# RASPBERRY_PI.net
KiCad netlist of a schematic drawn in Altium Designer
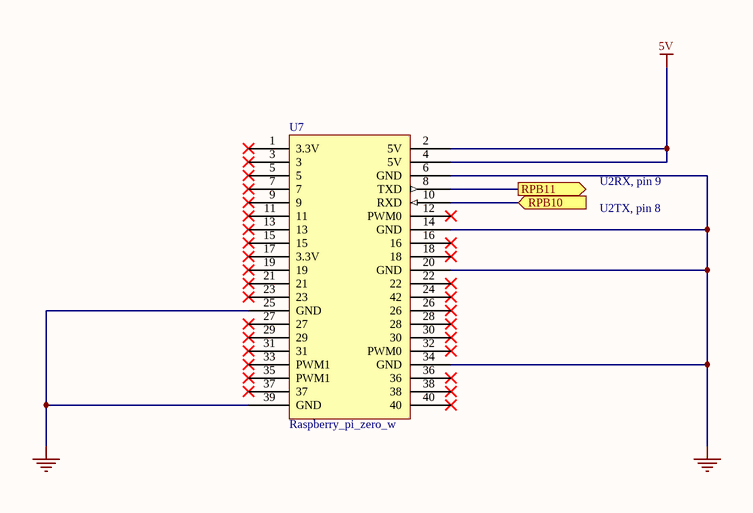
[diagram p0: RASPBERRY_PI.SchDoc]

(export (version "E")
  (design (tool "Eeschema 10.0.6"))
  (components
    (comp (ref "U7")
      (value "Raspberry_pi_zero_w")
      (footprint "RASPB")
      (libsource (lib "Schlib1") (part "Raspberry_pi_zero_w"))
    )
  )
  (nets
    (net (code "1") (name "/RPB10") (class "Default")
      (node (ref "U7") (pin "10") (pinfunction "RXD_10") (pintype "input"))
    )
    (net (code "2") (name "/RPB11") (class "Default")
      (node (ref "U7") (pin "8") (pinfunction "TXD_8") (pintype "output"))
    )
    (net (code "3") (name "5V") (class "Default")
      (node (ref "U7") (pin "2") (pinfunction "5V_2") (pintype "power_in"))
      (node (ref "U7") (pin "4") (pinfunction "5V_4") (pintype "power_in"))
    )
    (net (code "4") (name "GND") (class "Default")
      (node (ref "U7") (pin "14") (pinfunction "GND_14") (pintype "power_in"))
      (node (ref "U7") (pin "20") (pinfunction "GND_20") (pintype "power_in"))
      (node (ref "U7") (pin "25") (pinfunction "GND_25") (pintype "power_in"))
      (node (ref "U7") (pin "34") (pinfunction "GND_34") (pintype "power_in"))
      (node (ref "U7") (pin "39") (pinfunction "GND_39") (pintype "power_in"))
      (node (ref "U7") (pin "6") (pinfunction "GND_6") (pintype "power_in"))
    )
    (net (code "5") (name "unconnected-(U7-3.3V-Pad1)") (class "Default")
      (node (ref "U7") (pin "1") (pinfunction "3.3V_1") (pintype "power_in+no_connect"))
    )
    (net (code "6") (name "unconnected-(U7-3.3V-Pad17)") (class "Default")
      (node (ref "U7") (pin "17") (pinfunction "3.3V_17") (pintype "power_in+no_connect"))
    )
    (net (code "7") (name "unconnected-(U7-42-Pad24)") (class "Default")
      (node (ref "U7") (pin "24") (pinfunction "42_24") (pintype "passive+no_connect"))
    )
    (net (code "8") (name "unconnected-(U7-PWM0-Pad12)") (class "Default")
      (node (ref "U7") (pin "12") (pinfunction "PWM0_12") (pintype "passive+no_connect"))
    )
    (net (code "9") (name "unconnected-(U7-PWM0-Pad32)") (class "Default")
      (node (ref "U7") (pin "32") (pinfunction "PWM0_32") (pintype "passive+no_connect"))
    )
    (net (code "10") (name "unconnected-(U7-PWM1-Pad33)") (class "Default")
      (node (ref "U7") (pin "33") (pinfunction "PWM1_33") (pintype "passive+no_connect"))
    )
    (net (code "11") (name "unconnected-(U7-PWM1-Pad35)") (class "Default")
      (node (ref "U7") (pin "35") (pinfunction "PWM1_35") (pintype "passive+no_connect"))
    )
    (net (code "12") (name "unconnected-(U7-Pad3)") (class "Default")
      (node (ref "U7") (pin "3") (pinfunction "3_3") (pintype "passive+no_connect"))
    )
    (net (code "13") (name "unconnected-(U7-Pad5)") (class "Default")
      (node (ref "U7") (pin "5") (pinfunction "5_5") (pintype "passive+no_connect"))
    )
    (net (code "14") (name "unconnected-(U7-Pad7)") (class "Default")
      (node (ref "U7") (pin "7") (pinfunction "7_7") (pintype "passive+no_connect"))
    )
    (net (code "15") (name "unconnected-(U7-Pad9)") (class "Default")
      (node (ref "U7") (pin "9") (pinfunction "9_9") (pintype "passive+no_connect"))
    )
    (net (code "16") (name "unconnected-(U7-Pad11)") (class "Default")
      (node (ref "U7") (pin "11") (pinfunction "11_11") (pintype "passive+no_connect"))
    )
    (net (code "17") (name "unconnected-(U7-Pad13)") (class "Default")
      (node (ref "U7") (pin "13") (pinfunction "13_13") (pintype "passive+no_connect"))
    )
    (net (code "18") (name "unconnected-(U7-Pad15)") (class "Default")
      (node (ref "U7") (pin "15") (pinfunction "15_15") (pintype "passive+no_connect"))
    )
    (net (code "19") (name "unconnected-(U7-Pad16)") (class "Default")
      (node (ref "U7") (pin "16") (pinfunction "16_16") (pintype "passive+no_connect"))
    )
    (net (code "20") (name "unconnected-(U7-Pad18)") (class "Default")
      (node (ref "U7") (pin "18") (pinfunction "18_18") (pintype "passive+no_connect"))
    )
    (net (code "21") (name "unconnected-(U7-Pad19)") (class "Default")
      (node (ref "U7") (pin "19") (pinfunction "19_19") (pintype "passive+no_connect"))
    )
    (net (code "22") (name "unconnected-(U7-Pad21)") (class "Default")
      (node (ref "U7") (pin "21") (pinfunction "21_21") (pintype "passive+no_connect"))
    )
    (net (code "23") (name "unconnected-(U7-Pad22)") (class "Default")
      (node (ref "U7") (pin "22") (pinfunction "22_22") (pintype "passive+no_connect"))
    )
    (net (code "24") (name "unconnected-(U7-Pad23)") (class "Default")
      (node (ref "U7") (pin "23") (pinfunction "23_23") (pintype "passive+no_connect"))
    )
    (net (code "25") (name "unconnected-(U7-Pad26)") (class "Default")
      (node (ref "U7") (pin "26") (pinfunction "26_26") (pintype "passive+no_connect"))
    )
    (net (code "26") (name "unconnected-(U7-Pad27)") (class "Default")
      (node (ref "U7") (pin "27") (pinfunction "27_27") (pintype "passive+no_connect"))
    )
    (net (code "27") (name "unconnected-(U7-Pad28)") (class "Default")
      (node (ref "U7") (pin "28") (pinfunction "28_28") (pintype "passive+no_connect"))
    )
    (net (code "28") (name "unconnected-(U7-Pad29)") (class "Default")
      (node (ref "U7") (pin "29") (pinfunction "29_29") (pintype "passive+no_connect"))
    )
    (net (code "29") (name "unconnected-(U7-Pad30)") (class "Default")
      (node (ref "U7") (pin "30") (pinfunction "30_30") (pintype "passive+no_connect"))
    )
    (net (code "30") (name "unconnected-(U7-Pad31)") (class "Default")
      (node (ref "U7") (pin "31") (pinfunction "31_31") (pintype "passive+no_connect"))
    )
    (net (code "31") (name "unconnected-(U7-Pad36)") (class "Default")
      (node (ref "U7") (pin "36") (pinfunction "36_36") (pintype "passive+no_connect"))
    )
    (net (code "32") (name "unconnected-(U7-Pad37)") (class "Default")
      (node (ref "U7") (pin "37") (pinfunction "37_37") (pintype "passive+no_connect"))
    )
    (net (code "33") (name "unconnected-(U7-Pad38)") (class "Default")
      (node (ref "U7") (pin "38") (pinfunction "38_38") (pintype "passive+no_connect"))
    )
    (net (code "34") (name "unconnected-(U7-Pad40)") (class "Default")
      (node (ref "U7") (pin "40") (pinfunction "40_40") (pintype "passive+no_connect"))
    )
  )
)
